# ESP32.net
KiCad netlist of a schematic drawn in EasyEDA
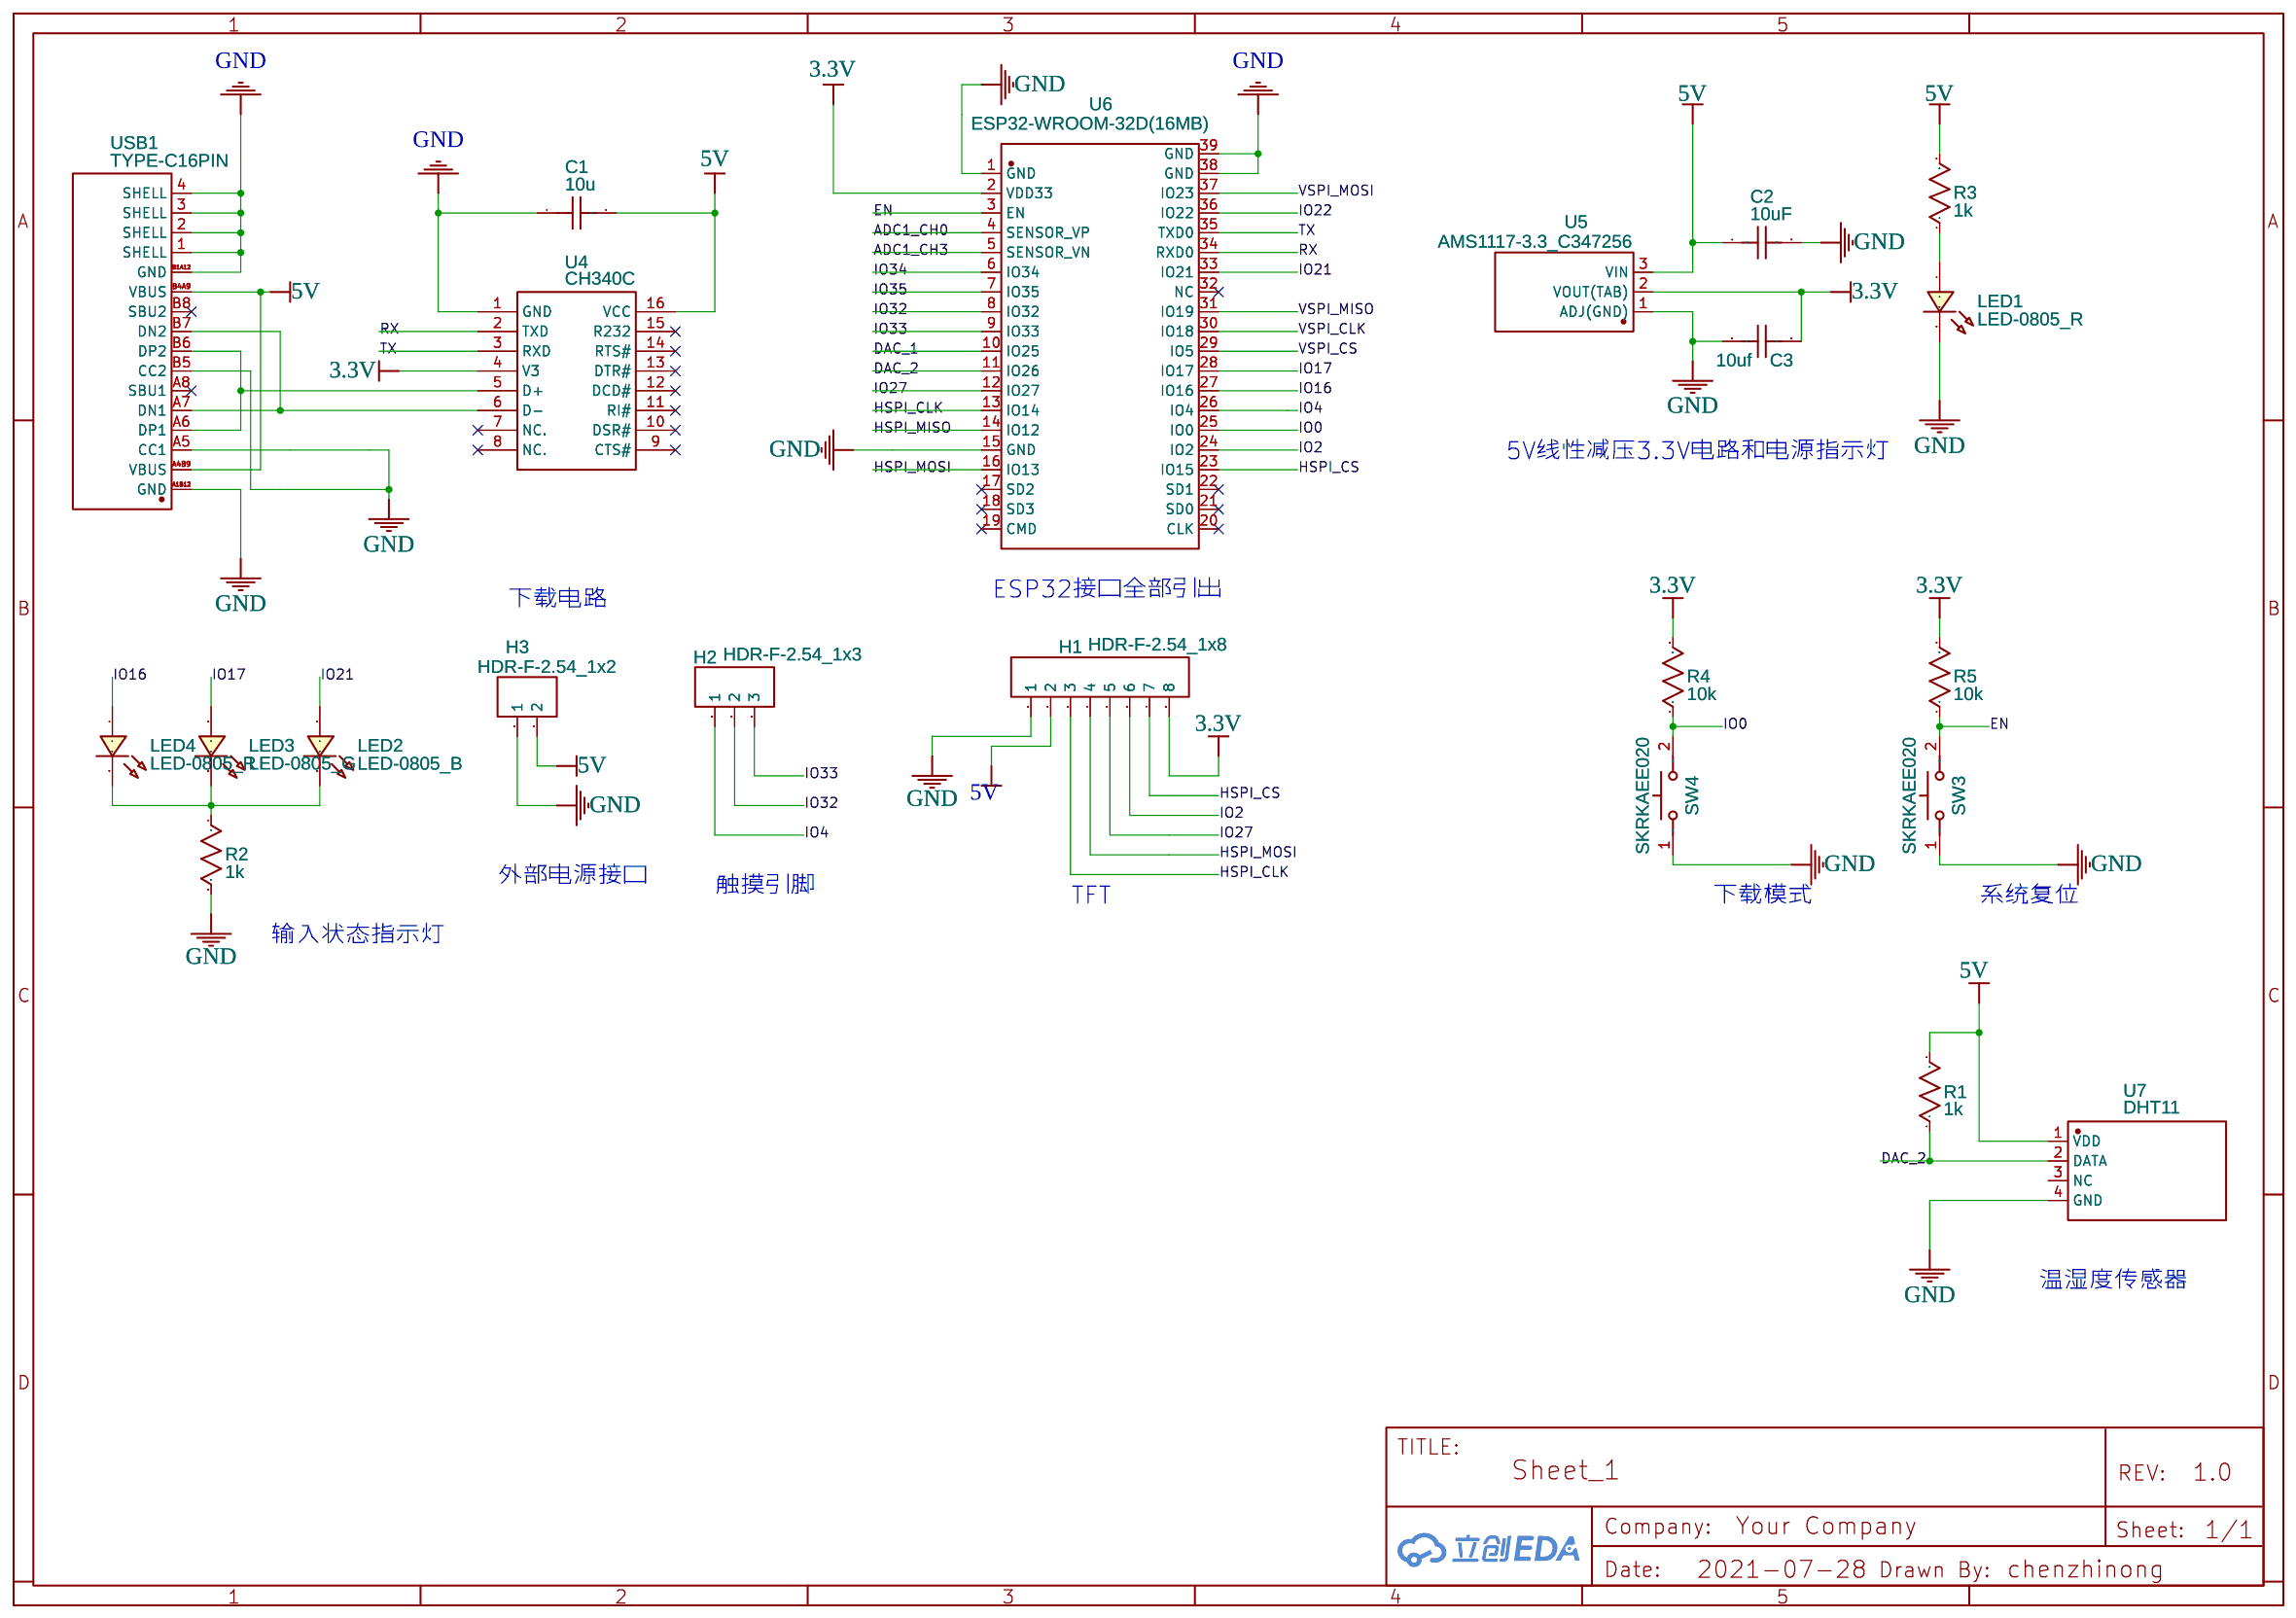
[diagram p0: schematic sheet]

(export (version "E")
  (design (tool "Eeschema 10.0.6"))
  (components
    (comp (ref "C1") (value "10u") (libsource (lib "") (part "C_0603_US_1")))
    (comp (ref "C2") (value "10uF") (libsource (lib "") (part "C_0603_US_1")))
    (comp (ref "C3") (value "10uf") (libsource (lib "") (part "C_0603_US")))
    (comp (ref "H1")
      (value "HDR-F-2.54_1x8")
      (fields (field (name "BOM_Supplier Part") "C225505"))
      (libsource (lib "") (part "HDR-F-2.54_1x8"))
    )
    (comp (ref "H2")
      (value "HDR-F-2.54_1x3")
      (fields (field (name "BOM_Supplier Part") "C146690"))
      (libsource (lib "") (part "HDR-F-2.54_1x3"))
    )
    (comp (ref "H3")
      (value "HDR-F-2.54_1x2")
      (fields (field (name "BOM_Supplier Part") "C49661"))
      (libsource (lib "") (part "HDR-F-2.54_1x2"))
    )
    (comp (ref "LED1")
      (value "LED-0805_R")
      (fields
        (field (name "BOM_Manufacturer Part") "17-21SURC/S530-A3/TR8")
        (field (name "BOM_Supplier Part") "C72037")
      )
      (libsource (lib "") (part "LED-0805_R"))
    )
    (comp (ref "LED2")
      (value "LED-0805_B")
      (fields
        (field (name "BOM_Manufacturer Part") "D-B080508B1-KS2")
        (field (name "BOM_Supplier Part") "C108412")
      )
      (libsource (lib "") (part "LED-0805_B"))
    )
    (comp (ref "LED3")
      (value "LED-0805_G")
      (fields (field (name "BOM_Manufacturer Part") "NCD0805G1") (field (name "BOM_Supplier Part") "C84260"))
      (libsource (lib "") (part "LED-0805_G"))
    )
    (comp (ref "LED4")
      (value "LED-0805_R")
      (fields
        (field (name "BOM_Manufacturer Part") "17-21SURC/S530-A3/TR8")
        (field (name "BOM_Supplier Part") "C72037")
      )
      (libsource (lib "") (part "LED-0805_R"))
    )
    (comp (ref "R1") (value "1k") (libsource (lib "") (part "R_0805_US")))
    (comp (ref "R2") (value "1k") (libsource (lib "") (part "R_0805_US_1")))
    (comp (ref "R3") (value "1k") (libsource (lib "") (part "R_0603_US")))
    (comp (ref "R4") (value "10k") (libsource (lib "") (part "R_0805_US")))
    (comp (ref "R5") (value "10k") (libsource (lib "") (part "R_0805_US")))
    (comp (ref "SW3")
      (value "SKRKAEE020")
      (fields (field (name "BOM_Supplier Part") "C115357"))
      (libsource (lib "") (part "SKRKAEE020"))
    )
    (comp (ref "SW4")
      (value "SKRKAEE020")
      (fields (field (name "BOM_Supplier Part") "C115357"))
      (libsource (lib "") (part "SKRKAEE020"))
    )
    (comp (ref "U4")
      (value "CH340C")
      (fields (field (name "BOM_Supplier Part") "C84681"))
      (libsource (lib "") (part "CH340C"))
    )
    (comp (ref "U5")
      (value "AMS1117-3.3_C347256")
      (fields
        (field (name "BOM_Manufacturer Part") "AMS1117-3.3")
        (field (name "BOM_Supplier Part") "C347256")
      )
      (libsource (lib "") (part "AMS1117-3.3_C347256"))
    )
    (comp (ref "U6")
      (value "ESP32-WROOM-32D(16MB)")
      (fields (field (name "BOM_Supplier Part") "C529578"))
      (libsource (lib "") (part "ESP32-WROOM-32D(16MB)"))
    )
    (comp (ref "U7")
      (value "DHT11")
      (fields (field (name "BOM_Supplier Part") "C117051"))
      (libsource (lib "") (part "DHT11"))
    )
    (comp (ref "USB1")
      (value "TYPE-C16PIN")
      (fields (field (name "BOM_Supplier Part") "C393939"))
      (libsource (lib "") (part "TYPE-C16PIN"))
    )
  )
  (nets
    (net (code "1") (name "/ADC1_CH0") (class "Default")
      (node (ref "U6") (pin "4") (pinfunction "SENSOR_VP_4") (pintype "unspecified"))
    )
    (net (code "2") (name "/ADC1_CH3") (class "Default")
      (node (ref "U6") (pin "5") (pinfunction "SENSOR_VN_5") (pintype "unspecified"))
    )
    (net (code "3") (name "/DAC_1") (class "Default")
      (node (ref "U6") (pin "10") (pinfunction "IO25_10") (pintype "unspecified"))
    )
    (net (code "4") (name "/DAC_2") (class "Default")
      (node (ref "R1") (pin "1") (pinfunction "1_1") (pintype "unspecified"))
      (node (ref "U6") (pin "11") (pinfunction "IO26_11") (pintype "unspecified"))
      (node (ref "U7") (pin "2") (pinfunction "DATA_2") (pintype "unspecified"))
    )
    (net (code "5") (name "/EN") (class "Default")
      (node (ref "R5") (pin "1") (pinfunction "1_1") (pintype "unspecified"))
      (node (ref "SW3") (pin "2") (pinfunction "2_2") (pintype "unspecified"))
      (node (ref "U6") (pin "3") (pinfunction "EN_3") (pintype "unspecified"))
    )
    (net (code "6") (name "/HSPI_CLK") (class "Default")
      (node (ref "H1") (pin "3") (pinfunction "3_3") (pintype "unspecified"))
      (node (ref "U6") (pin "13") (pinfunction "IO14_13") (pintype "unspecified"))
    )
    (net (code "7") (name "/HSPI_CS") (class "Default")
      (node (ref "H1") (pin "7") (pinfunction "7_7") (pintype "unspecified"))
      (node (ref "U6") (pin "23") (pinfunction "IO15_23") (pintype "unspecified"))
    )
    (net (code "8") (name "/HSPI_MISO") (class "Default")
      (node (ref "U6") (pin "14") (pinfunction "IO12_14") (pintype "unspecified"))
    )
    (net (code "9") (name "/HSPI_MOSI") (class "Default")
      (node (ref "H1") (pin "4") (pinfunction "4_4") (pintype "unspecified"))
      (node (ref "U6") (pin "16") (pinfunction "IO13_16") (pintype "unspecified"))
    )
    (net (code "10") (name "/IO0") (class "Default")
      (node (ref "R4") (pin "1") (pinfunction "1_1") (pintype "unspecified"))
      (node (ref "SW4") (pin "2") (pinfunction "2_2") (pintype "unspecified"))
      (node (ref "U6") (pin "25") (pinfunction "IO0_25") (pintype "unspecified"))
    )
    (net (code "11") (name "/IO2") (class "Default")
      (node (ref "H1") (pin "6") (pinfunction "6_6") (pintype "unspecified"))
      (node (ref "U6") (pin "24") (pinfunction "IO2_24") (pintype "unspecified"))
    )
    (net (code "12") (name "/IO4") (class "Default")
      (node (ref "H2") (pin "1") (pinfunction "1_1") (pintype "input"))
      (node (ref "U6") (pin "26") (pinfunction "IO4_26") (pintype "unspecified"))
    )
    (net (code "13") (name "/IO16") (class "Default")
      (node (ref "LED4") (pin "1") (pinfunction "1_1") (pintype "unspecified"))
      (node (ref "U6") (pin "27") (pinfunction "IO16_27") (pintype "unspecified"))
    )
    (net (code "14") (name "/IO17") (class "Default")
      (node (ref "LED3") (pin "1") (pinfunction "1_1") (pintype "unspecified"))
      (node (ref "U6") (pin "28") (pinfunction "IO17_28") (pintype "unspecified"))
    )
    (net (code "15") (name "/IO21") (class "Default")
      (node (ref "LED2") (pin "1") (pinfunction "1_1") (pintype "unspecified"))
      (node (ref "U6") (pin "33") (pinfunction "IO21_33") (pintype "unspecified"))
    )
    (net (code "16") (name "/IO22") (class "Default")
      (node (ref "U6") (pin "36") (pinfunction "IO22_36") (pintype "unspecified"))
    )
    (net (code "17") (name "/IO27") (class "Default")
      (node (ref "H1") (pin "5") (pinfunction "5_5") (pintype "unspecified"))
      (node (ref "U6") (pin "12") (pinfunction "IO27_12") (pintype "unspecified"))
    )
    (net (code "18") (name "/IO32") (class "Default")
      (node (ref "H2") (pin "2") (pinfunction "2_2") (pintype "input"))
      (node (ref "U6") (pin "8") (pinfunction "IO32_8") (pintype "unspecified"))
    )
    (net (code "19") (name "/IO33") (class "Default")
      (node (ref "H2") (pin "3") (pinfunction "3_3") (pintype "input"))
      (node (ref "U6") (pin "9") (pinfunction "IO33_9") (pintype "unspecified"))
    )
    (net (code "20") (name "/IO34") (class "Default")
      (node (ref "U6") (pin "6") (pinfunction "IO34_6") (pintype "unspecified"))
    )
    (net (code "21") (name "/IO35") (class "Default")
      (node (ref "U6") (pin "7") (pinfunction "IO35_7") (pintype "unspecified"))
    )
    (net (code "22") (name "/RX") (class "Default")
      (node (ref "U4") (pin "2") (pinfunction "TXD_2") (pintype "unspecified"))
      (node (ref "U6") (pin "34") (pinfunction "RXD0_34") (pintype "unspecified"))
    )
    (net (code "23") (name "/TX") (class "Default")
      (node (ref "U4") (pin "3") (pinfunction "RXD_3") (pintype "unspecified"))
      (node (ref "U6") (pin "35") (pinfunction "TXD0_35") (pintype "unspecified"))
    )
    (net (code "24") (name "/VSPI_CLK") (class "Default")
      (node (ref "U6") (pin "30") (pinfunction "IO18_30") (pintype "unspecified"))
    )
    (net (code "25") (name "/VSPI_CS") (class "Default")
      (node (ref "U6") (pin "29") (pinfunction "IO5_29") (pintype "unspecified"))
    )
    (net (code "26") (name "/VSPI_MISO") (class "Default")
      (node (ref "U6") (pin "31") (pinfunction "IO19_31") (pintype "unspecified"))
    )
    (net (code "27") (name "/VSPI_MOSI") (class "Default")
      (node (ref "U6") (pin "37") (pinfunction "IO23_37") (pintype "unspecified"))
    )
    (net (code "28") (name "3.3V") (class "Default")
      (node (ref "C3") (pin "1") (pinfunction "1_1") (pintype "unspecified"))
      (node (ref "H1") (pin "8") (pinfunction "8_8") (pintype "unspecified"))
      (node (ref "R4") (pin "2") (pinfunction "2_2") (pintype "unspecified"))
      (node (ref "R5") (pin "2") (pinfunction "2_2") (pintype "unspecified"))
      (node (ref "U4") (pin "4") (pinfunction "V3_4") (pintype "unspecified"))
      (node (ref "U5") (pin "2") (pinfunction "VOUT(TAB)_2") (pintype "unspecified"))
      (node (ref "U6") (pin "2") (pinfunction "VDD33_2") (pintype "unspecified"))
    )
    (net (code "29") (name "5V") (class "Default")
      (node (ref "C1") (pin "2") (pinfunction "2_2") (pintype "unspecified"))
      (node (ref "C2") (pin "1") (pinfunction "1_1") (pintype "unspecified"))
      (node (ref "H1") (pin "2") (pinfunction "2_2") (pintype "unspecified"))
      (node (ref "H3") (pin "2") (pinfunction "2_2") (pintype "input"))
      (node (ref "R1") (pin "2") (pinfunction "2_2") (pintype "unspecified"))
      (node (ref "R3") (pin "2") (pinfunction "2_2") (pintype "unspecified"))
      (node (ref "U4") (pin "16") (pinfunction "VCC_16") (pintype "unspecified"))
      (node (ref "U5") (pin "3") (pinfunction "VIN_3") (pintype "unspecified"))
      (node (ref "U7") (pin "1") (pinfunction "VDD_1") (pintype "unspecified"))
      (node (ref "USB1") (pin "A4B9") (pinfunction "VBUS_A4B9") (pintype "unspecified"))
      (node (ref "USB1") (pin "B4A9") (pinfunction "VBUS_B4A9") (pintype "unspecified"))
    )
    (net (code "30") (name "GND") (class "Default")
      (node (ref "C1") (pin "1") (pinfunction "1_1") (pintype "unspecified"))
      (node (ref "C2") (pin "2") (pinfunction "2_2") (pintype "unspecified"))
      (node (ref "C3") (pin "2") (pinfunction "2_2") (pintype "unspecified"))
      (node (ref "H1") (pin "1") (pinfunction "1_1") (pintype "unspecified"))
      (node (ref "H3") (pin "1") (pinfunction "1_1") (pintype "input"))
      (node (ref "LED1") (pin "2") (pinfunction "2_2") (pintype "unspecified"))
      (node (ref "R2") (pin "2") (pinfunction "2_2") (pintype "unspecified"))
      (node (ref "SW3") (pin "1") (pinfunction "1_1") (pintype "unspecified"))
      (node (ref "SW4") (pin "1") (pinfunction "1_1") (pintype "unspecified"))
      (node (ref "U4") (pin "1") (pinfunction "GND_1") (pintype "unspecified"))
      (node (ref "U5") (pin "1") (pinfunction "ADJ(GND)_1") (pintype "unspecified"))
      (node (ref "U6") (pin "1") (pinfunction "GND_1") (pintype "unspecified"))
      (node (ref "U6") (pin "15") (pinfunction "GND_15") (pintype "unspecified"))
      (node (ref "U6") (pin "38") (pinfunction "GND_38") (pintype "unspecified"))
      (node (ref "U6") (pin "39") (pinfunction "GND_39") (pintype "unspecified"))
      (node (ref "U7") (pin "4") (pinfunction "GND_4") (pintype "unspecified"))
      (node (ref "USB1") (pin "1") (pinfunction "SHELL_1") (pintype "unspecified"))
      (node (ref "USB1") (pin "2") (pinfunction "SHELL_2") (pintype "unspecified"))
      (node (ref "USB1") (pin "3") (pinfunction "SHELL_3") (pintype "unspecified"))
      (node (ref "USB1") (pin "4") (pinfunction "SHELL_4") (pintype "unspecified"))
      (node (ref "USB1") (pin "A1B12") (pinfunction "GND_A1B12") (pintype "unspecified"))
      (node (ref "USB1") (pin "A5") (pinfunction "CC1_A5") (pintype "unspecified"))
      (node (ref "USB1") (pin "B1A12") (pinfunction "GND_B1A12") (pintype "unspecified"))
      (node (ref "USB1") (pin "B5") (pinfunction "CC2_B5") (pintype "unspecified"))
    )
    (net (code "31") (name "Net-(LED1-Pad1)") (class "Default")
      (node (ref "LED1") (pin "1") (pinfunction "1_1") (pintype "unspecified"))
      (node (ref "R3") (pin "1") (pinfunction "1_1") (pintype "unspecified"))
    )
    (net (code "32") (name "Net-(LED2-Pad2)") (class "Default")
      (node (ref "LED2") (pin "2") (pinfunction "2_2") (pintype "unspecified"))
      (node (ref "LED3") (pin "2") (pinfunction "2_2") (pintype "unspecified"))
      (node (ref "LED4") (pin "2") (pinfunction "2_2") (pintype "unspecified"))
      (node (ref "R2") (pin "1") (pinfunction "1_1") (pintype "unspecified"))
    )
    (net (code "33") (name "Net-(U4-D+)") (class "Default")
      (node (ref "U4") (pin "5") (pinfunction "D+_5") (pintype "unspecified"))
      (node (ref "USB1") (pin "A6") (pinfunction "DP1_A6") (pintype "unspecified"))
      (node (ref "USB1") (pin "B6") (pinfunction "DP2_B6") (pintype "unspecified"))
    )
    (net (code "34") (name "Net-(U4-D-)") (class "Default")
      (node (ref "U4") (pin "6") (pinfunction "D-_6") (pintype "unspecified"))
      (node (ref "USB1") (pin "A7") (pinfunction "DN1_A7") (pintype "unspecified"))
      (node (ref "USB1") (pin "B7") (pinfunction "DN2_B7") (pintype "unspecified"))
    )
    (net (code "35") (name "unconnected-(U4-CTS#-Pad9)") (class "Default")
      (node (ref "U4") (pin "9") (pinfunction "CTS#_9") (pintype "unspecified+no_connect"))
    )
    (net (code "36") (name "unconnected-(U4-DCD#-Pad12)") (class "Default")
      (node (ref "U4") (pin "12") (pinfunction "DCD#_12") (pintype "unspecified+no_connect"))
    )
    (net (code "37") (name "unconnected-(U4-DSR#-Pad10)") (class "Default")
      (node (ref "U4") (pin "10") (pinfunction "DSR#_10") (pintype "unspecified+no_connect"))
    )
    (net (code "38") (name "unconnected-(U4-DTR#-Pad13)") (class "Default")
      (node (ref "U4") (pin "13") (pinfunction "DTR#_13") (pintype "unspecified+no_connect"))
    )
    (net (code "39") (name "unconnected-(U4-NC.-Pad7)") (class "Default")
      (node (ref "U4") (pin "7") (pinfunction "NC._7") (pintype "unspecified+no_connect"))
    )
    (net (code "40") (name "unconnected-(U4-NC.-Pad8)") (class "Default")
      (node (ref "U4") (pin "8") (pinfunction "NC._8") (pintype "unspecified+no_connect"))
    )
    (net (code "41") (name "unconnected-(U4-R232-Pad15)") (class "Default")
      (node (ref "U4") (pin "15") (pinfunction "R232_15") (pintype "unspecified+no_connect"))
    )
    (net (code "42") (name "unconnected-(U4-RI#-Pad11)") (class "Default")
      (node (ref "U4") (pin "11") (pinfunction "RI#_11") (pintype "unspecified+no_connect"))
    )
    (net (code "43") (name "unconnected-(U4-RTS#-Pad14)") (class "Default")
      (node (ref "U4") (pin "14") (pinfunction "RTS#_14") (pintype "unspecified+no_connect"))
    )
    (net (code "44") (name "unconnected-(U6-CLK-Pad20)") (class "Default")
      (node (ref "U6") (pin "20") (pinfunction "CLK_20") (pintype "unspecified+no_connect"))
    )
    (net (code "45") (name "unconnected-(U6-CMD-Pad19)") (class "Default")
      (node (ref "U6") (pin "19") (pinfunction "CMD_19") (pintype "unspecified+no_connect"))
    )
    (net (code "46") (name "unconnected-(U6-NC-Pad32)") (class "Default")
      (node (ref "U6") (pin "32") (pinfunction "NC_32") (pintype "unspecified+no_connect"))
    )
    (net (code "47") (name "unconnected-(U6-SD0-Pad21)") (class "Default")
      (node (ref "U6") (pin "21") (pinfunction "SD0_21") (pintype "unspecified+no_connect"))
    )
    (net (code "48") (name "unconnected-(U6-SD1-Pad22)") (class "Default")
      (node (ref "U6") (pin "22") (pinfunction "SD1_22") (pintype "unspecified+no_connect"))
    )
    (net (code "49") (name "unconnected-(U6-SD2-Pad17)") (class "Default")
      (node (ref "U6") (pin "17") (pinfunction "SD2_17") (pintype "unspecified+no_connect"))
    )
    (net (code "50") (name "unconnected-(U6-SD3-Pad18)") (class "Default")
      (node (ref "U6") (pin "18") (pinfunction "SD3_18") (pintype "unspecified+no_connect"))
    )
    (net (code "51") (name "unconnected-(U7-NC-Pad3)") (class "Default")
      (node (ref "U7") (pin "3") (pinfunction "NC_3") (pintype "unspecified"))
    )
    (net (code "52") (name "unconnected-(USB1-SBU1-PadA8)") (class "Default")
      (node (ref "USB1") (pin "A8") (pinfunction "SBU1_A8") (pintype "unspecified+no_connect"))
    )
    (net (code "53") (name "unconnected-(USB1-SBU2-PadB8)") (class "Default")
      (node (ref "USB1") (pin "B8") (pinfunction "SBU2_B8") (pintype "unspecified+no_connect"))
    )
  )
)
